# USB_Hug.net
KiCad netlist of a schematic drawn in EasyEDA Pro
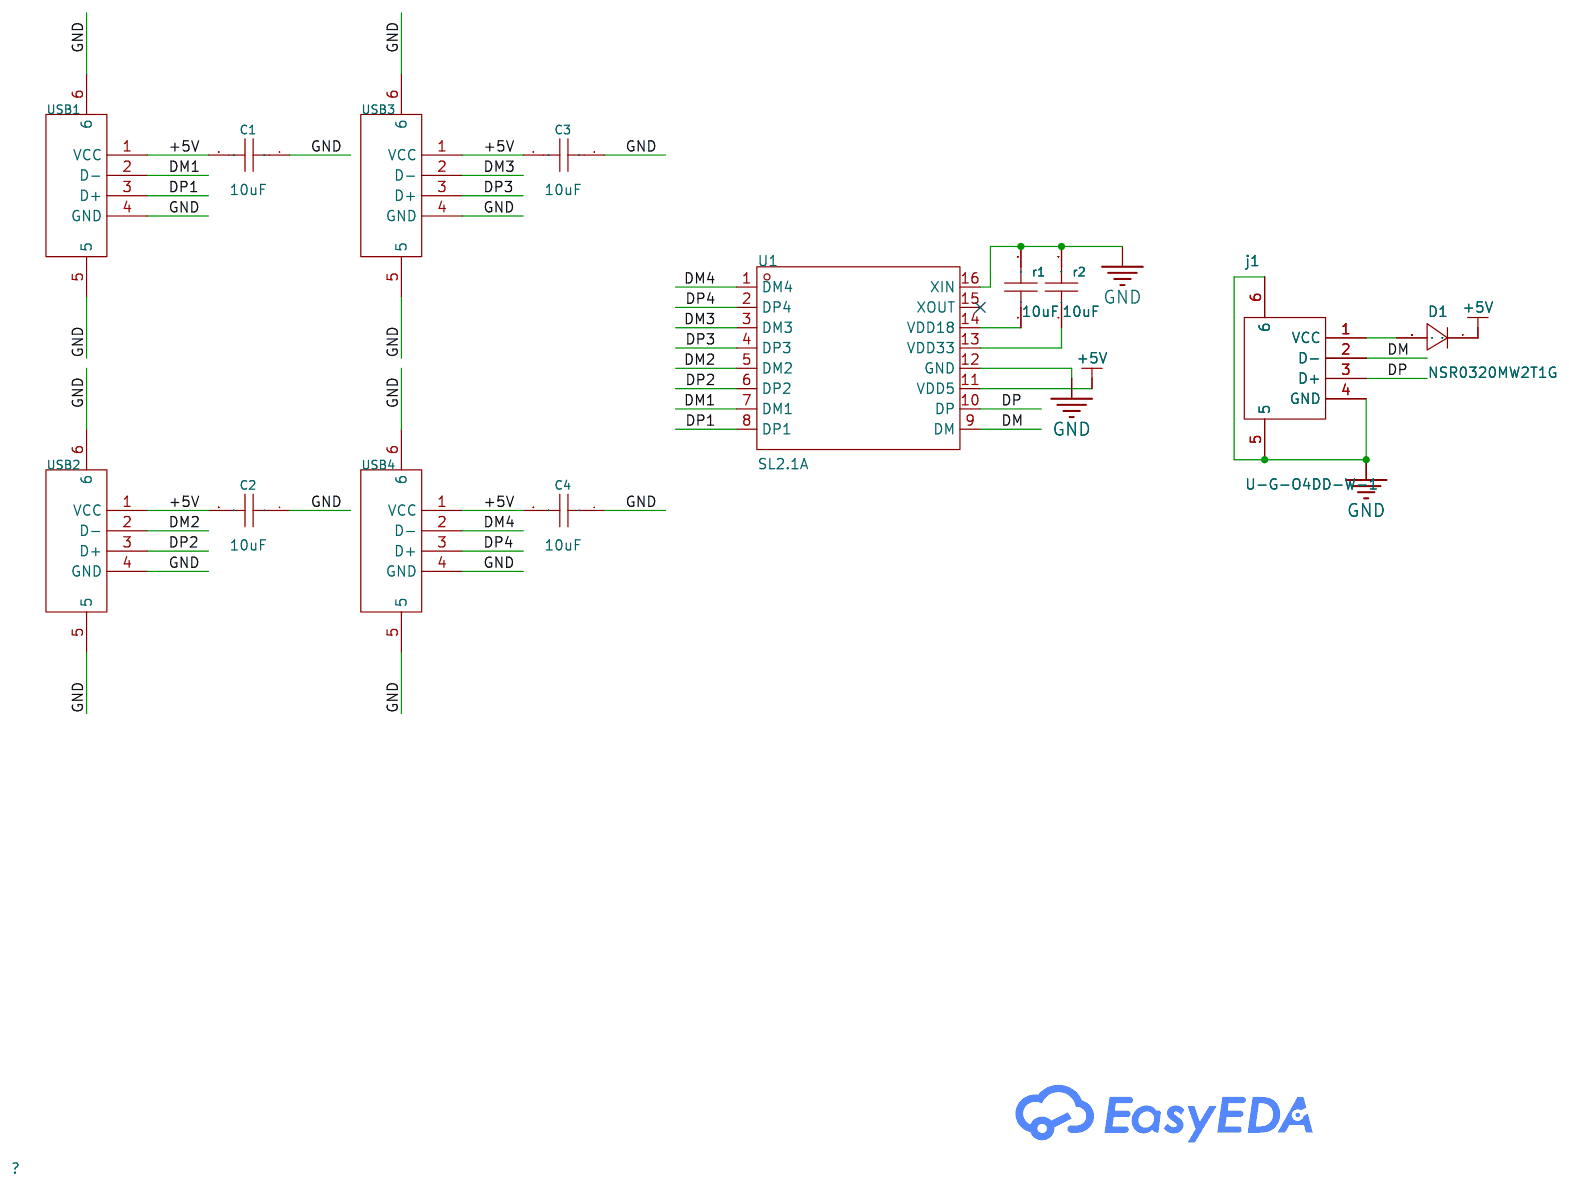
[diagram p0: schematic sheet]

(export (version "E")
  (design (tool "Eeschema 10.0.6"))
  (components
    (comp (ref "C1")
      (value "10uF")
      (footprint "easyedapro:C0603")
      (description "Capacitance:10uF Tolerance:±20% Tolerance:±20% Voltage Rating:25V Temperature Coefficient:X5R")
      (fields
        (field (name "Manufacturer Part") "CL10A106MA8NRNC")
        (field (name "Manufacturer") "SAMSUNG(三星)")
      )
      (libsource (lib "easyedapro") (part "CL10A106MA8NRNC"))
    )
    (comp (ref "C2")
      (value "10uF")
      (footprint "easyedapro:C0603")
      (description "Capacitance:10uF Tolerance:±20% Tolerance:±20% Voltage Rating:25V Temperature Coefficient:X5R")
      (fields
        (field (name "Manufacturer Part") "CL10A106MA8NRNC")
        (field (name "Manufacturer") "SAMSUNG(三星)")
      )
      (libsource (lib "easyedapro") (part "CL10A106MA8NRNC"))
    )
    (comp (ref "C3")
      (value "10uF")
      (footprint "easyedapro:C0603")
      (description "Capacitance:10uF Tolerance:±20% Tolerance:±20% Voltage Rating:25V Temperature Coefficient:X5R")
      (fields
        (field (name "Manufacturer Part") "CL10A106MA8NRNC")
        (field (name "Manufacturer") "SAMSUNG(三星)")
      )
      (libsource (lib "easyedapro") (part "CL10A106MA8NRNC"))
    )
    (comp (ref "C4")
      (value "10uF")
      (footprint "easyedapro:C0603")
      (description "Capacitance:10uF Tolerance:±20% Tolerance:±20% Voltage Rating:25V Temperature Coefficient:X5R")
      (fields
        (field (name "Manufacturer Part") "CL10A106MA8NRNC")
        (field (name "Manufacturer") "SAMSUNG(三星)")
      )
      (libsource (lib "easyedapro") (part "CL10A106MA8NRNC"))
    )
    (comp (ref "D1")
      (value "NSR0320MW2T1G")
      (footprint "easyedapro:SOD-323_L1.8-W1.3-LS2.5-RD")
      (fields (field (name "Manufacturer") "onsemi(安森美)"))
      (libsource (lib "easyedapro") (part "NSR0320MW2T1G"))
    )
    (comp (ref "j1")
      (value "U-G-O4DD-W-1")
      (footprint "easyedapro:USB-A-TH_U-G-04WD-W-01")
      (fields (field (name "Manufacturer") "韩国韩荣"))
      (libsource (lib "easyedapro") (part "U-G-04DD-W-01"))
    )
    (comp (ref "r1")
      (value "10uF")
      (footprint "easyedapro:C0603")
      (description "Capacitance:10uF Tolerance:±20% Tolerance:±20% Voltage Rating:25V Temperature Coefficient:X5R")
      (fields
        (field (name "Manufacturer Part") "CL10A106MA8NRNC")
        (field (name "Manufacturer") "SAMSUNG(三星)")
      )
      (libsource (lib "easyedapro") (part "CL10A106MA8NRNC"))
    )
    (comp (ref "r2")
      (value "10uF")
      (footprint "easyedapro:C0603")
      (description "Capacitance:10uF Tolerance:±20% Tolerance:±20% Voltage Rating:25V Temperature Coefficient:X5R")
      (fields
        (field (name "Manufacturer Part") "CL10A106MA8NRNC")
        (field (name "Manufacturer") "SAMSUNG(三星)")
      )
      (libsource (lib "easyedapro") (part "CL10A106MA8NRNC"))
    )
    (comp (ref "U1")
      (value "SL2.1A")
      (footprint "easyedapro:SOP-16_L10.0-W3.9-P1.27-LS6.0-BL")
      (fields (field (name "Manufacturer") "CoreChips(和芯润德)"))
      (libsource (lib "easyedapro") (part "SL2.1A"))
    )
    (comp (ref "USB1")
      (value "903-131A1011D10100")
      (footprint "easyedapro:USB-A-TH_C46407")
      (fields (field (name "Manufacturer") "精拓金"))
      (libsource (lib "easyedapro") (part "USB-AF-90-14.4X13.6-H7.0-DIP"))
    )
    (comp (ref "USB2")
      (value "903-131A1011D10100")
      (footprint "easyedapro:USB-A-TH_C46407")
      (fields (field (name "Manufacturer") "精拓金"))
      (libsource (lib "easyedapro") (part "USB-AF-90-14.4X13.6-H7.0-DIP"))
    )
    (comp (ref "USB3")
      (value "903-131A1011D10100")
      (footprint "easyedapro:USB-A-TH_C46407")
      (fields (field (name "Manufacturer") "精拓金"))
      (libsource (lib "easyedapro") (part "USB-AF-90-14.4X13.6-H7.0-DIP"))
    )
    (comp (ref "USB4")
      (value "903-131A1011D10100")
      (footprint "easyedapro:USB-A-TH_C46407")
      (fields (field (name "Manufacturer") "精拓金"))
      (libsource (lib "easyedapro") (part "USB-AF-90-14.4X13.6-H7.0-DIP"))
    )
  )
  (nets
    (net (code "1") (name "+5V") (class "Default")
      (node (ref "C1") (pin "2") (pinfunction "2_2") (pintype "input"))
      (node (ref "C2") (pin "2") (pinfunction "2_2") (pintype "input"))
      (node (ref "C3") (pin "2") (pinfunction "2_2") (pintype "input"))
      (node (ref "C4") (pin "2") (pinfunction "2_2") (pintype "input"))
      (node (ref "D1") (pin "1") (pinfunction "C_1") (pintype "unspecified"))
      (node (ref "U1") (pin "11") (pinfunction "VDD5_11") (pintype "unspecified"))
      (node (ref "USB1") (pin "1") (pinfunction "VCC_1") (pintype "input"))
      (node (ref "USB2") (pin "1") (pinfunction "VCC_1") (pintype "input"))
      (node (ref "USB3") (pin "1") (pinfunction "VCC_1") (pintype "input"))
      (node (ref "USB4") (pin "1") (pinfunction "VCC_1") (pintype "input"))
    )
    (net (code "2") (name "/DM") (class "Default")
      (node (ref "U1") (pin "9") (pinfunction "DM_9") (pintype "unspecified"))
      (node (ref "j1") (pin "2") (pinfunction "D-_2") (pintype "unspecified"))
    )
    (net (code "3") (name "/DM1") (class "Default")
      (node (ref "U1") (pin "7") (pinfunction "DM1_7") (pintype "unspecified"))
      (node (ref "USB1") (pin "2") (pinfunction "D-_2") (pintype "input"))
    )
    (net (code "4") (name "/DM2") (class "Default")
      (node (ref "U1") (pin "5") (pinfunction "DM2_5") (pintype "unspecified"))
      (node (ref "USB2") (pin "2") (pinfunction "D-_2") (pintype "input"))
    )
    (net (code "5") (name "/DM3") (class "Default")
      (node (ref "U1") (pin "3") (pinfunction "DM3_3") (pintype "unspecified"))
      (node (ref "USB3") (pin "2") (pinfunction "D-_2") (pintype "input"))
    )
    (net (code "6") (name "/DM4") (class "Default")
      (node (ref "U1") (pin "1") (pinfunction "DM4_1") (pintype "unspecified"))
      (node (ref "USB4") (pin "2") (pinfunction "D-_2") (pintype "input"))
    )
    (net (code "7") (name "/DP") (class "Default")
      (node (ref "U1") (pin "10") (pinfunction "DP_10") (pintype "unspecified"))
      (node (ref "j1") (pin "3") (pinfunction "D+_3") (pintype "unspecified"))
    )
    (net (code "8") (name "/DP1") (class "Default")
      (node (ref "U1") (pin "8") (pinfunction "DP1_8") (pintype "unspecified"))
      (node (ref "USB1") (pin "3") (pinfunction "D+_3") (pintype "input"))
    )
    (net (code "9") (name "/DP2") (class "Default")
      (node (ref "U1") (pin "6") (pinfunction "DP2_6") (pintype "unspecified"))
      (node (ref "USB2") (pin "3") (pinfunction "D+_3") (pintype "input"))
    )
    (net (code "10") (name "/DP3") (class "Default")
      (node (ref "U1") (pin "4") (pinfunction "DP3_4") (pintype "unspecified"))
      (node (ref "USB3") (pin "3") (pinfunction "D+_3") (pintype "input"))
    )
    (net (code "11") (name "/DP4") (class "Default")
      (node (ref "U1") (pin "2") (pinfunction "DP4_2") (pintype "unspecified"))
      (node (ref "USB4") (pin "3") (pinfunction "D+_3") (pintype "input"))
    )
    (net (code "12") (name "GND") (class "Default")
      (node (ref "C1") (pin "1") (pinfunction "1_1") (pintype "input"))
      (node (ref "C2") (pin "1") (pinfunction "1_1") (pintype "input"))
      (node (ref "C3") (pin "1") (pinfunction "1_1") (pintype "input"))
      (node (ref "C4") (pin "1") (pinfunction "1_1") (pintype "input"))
      (node (ref "U1") (pin "12") (pinfunction "GND_12") (pintype "unspecified"))
      (node (ref "U1") (pin "16") (pinfunction "XIN_16") (pintype "unspecified"))
      (node (ref "USB1") (pin "4") (pinfunction "GND_4") (pintype "input"))
      (node (ref "USB1") (pin "5") (pinfunction "5_5") (pintype "input"))
      (node (ref "USB1") (pin "6") (pinfunction "6_6") (pintype "input"))
      (node (ref "USB2") (pin "4") (pinfunction "GND_4") (pintype "input"))
      (node (ref "USB2") (pin "5") (pinfunction "5_5") (pintype "input"))
      (node (ref "USB2") (pin "6") (pinfunction "6_6") (pintype "input"))
      (node (ref "USB3") (pin "4") (pinfunction "GND_4") (pintype "input"))
      (node (ref "USB3") (pin "5") (pinfunction "5_5") (pintype "input"))
      (node (ref "USB3") (pin "6") (pinfunction "6_6") (pintype "input"))
      (node (ref "USB4") (pin "4") (pinfunction "GND_4") (pintype "input"))
      (node (ref "USB4") (pin "5") (pinfunction "5_5") (pintype "input"))
      (node (ref "USB4") (pin "6") (pinfunction "6_6") (pintype "input"))
      (node (ref "j1") (pin "4") (pinfunction "GND_4") (pintype "unspecified"))
      (node (ref "j1") (pin "5") (pinfunction "5_5") (pintype "unspecified"))
      (node (ref "j1") (pin "6") (pinfunction "6_6") (pintype "unspecified"))
      (node (ref "r1") (pin "2") (pinfunction "2_2") (pintype "input"))
      (node (ref "r2") (pin "2") (pinfunction "2_2") (pintype "input"))
    )
    (net (code "13") (name "Net-(D1-A)") (class "Default")
      (node (ref "D1") (pin "2") (pinfunction "A_2") (pintype "unspecified"))
      (node (ref "j1") (pin "1") (pinfunction "VCC_1") (pintype "unspecified"))
    )
    (net (code "14") (name "Net-(U1-VDD18)") (class "Default")
      (node (ref "U1") (pin "14") (pinfunction "VDD18_14") (pintype "unspecified"))
      (node (ref "r1") (pin "1") (pinfunction "1_1") (pintype "input"))
    )
    (net (code "15") (name "Net-(U1-VDD33)") (class "Default")
      (node (ref "U1") (pin "13") (pinfunction "VDD33_13") (pintype "unspecified"))
      (node (ref "r2") (pin "1") (pinfunction "1_1") (pintype "input"))
    )
    (net (code "16") (name "unconnected-(U1-XOUT-Pad15)") (class "Default")
      (node (ref "U1") (pin "15") (pinfunction "XOUT_15") (pintype "unspecified+no_connect"))
    )
  )
)
